# motor_control.net
KiCad netlist of a schematic drawn in Altium Designer
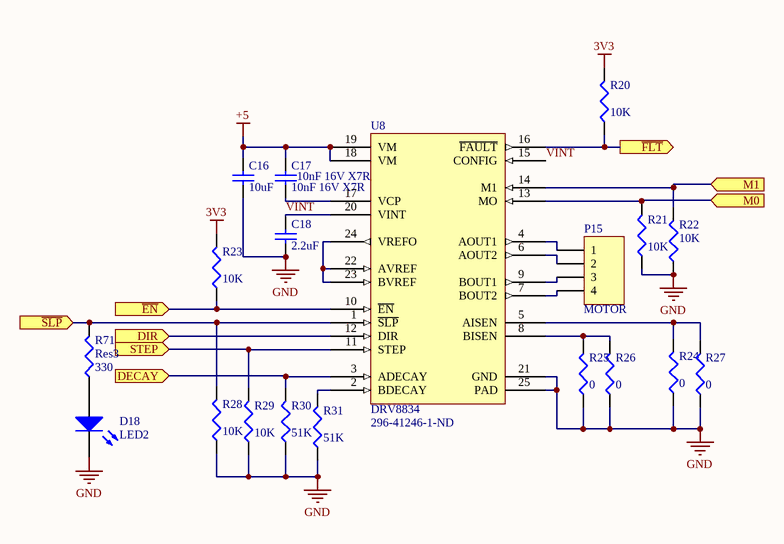
[diagram p0: motor_control.SchDoc]

(export (version "E")
  (design (tool "Eeschema 10.0.6"))
  (components
    (comp (ref "C16")
      (value "10uF")
      (footprint "1608[0603]")
      (description "Capacitor (Semiconductor SIM Model)")
      (fields (field (name "PUBLISHER") "Altium Limited"))
      (libsource (lib "Miscellaneous Devices") (part "Cap Semi"))
    )
    (comp (ref "C17")
      (value "10nF 16V X7R")
      (footprint "1608[0603]")
      (description "Capacitor (Semiconductor SIM Model)")
      (fields (field (name "ALTIUM_VALUE") "10nF 16V X7R") (field (name "PUBLISHER") "Altium Limited"))
      (libsource (lib "Miscellaneous Devices") (part "Cap Semi"))
    )
    (comp (ref "C18")
      (value "2.2uF")
      (footprint "1608[0603]")
      (description "Capacitor (Semiconductor SIM Model)")
      (fields (field (name "PUBLISHER") "Altium Limited"))
      (libsource (lib "Miscellaneous Devices") (part "Cap Semi"))
    )
    (comp (ref "D18")
      (value "LED2")
      (footprint "0603-LED")
      (description "Typical RED, GREEN, YELLOW, AMBER GaAs LED")
      (fields (field (name "PUBLISHER") "Altium Limited"))
      (libsource (lib "Miscellaneous Devices") (part "LED2"))
    )
    (comp (ref "P15")
      (value "MOTOR")
      (footprint "DF14-4P-1.25H(55)")
      (description "Header, 4-Pin")
      (fields (field (name "PUBLISHER") "Altium Limited"))
      (libsource (lib "Miscellaneous Connectors") (part "Header 4"))
    )
    (comp (ref "R20")
      (value "10K")
      (footprint "J1-0603")
      (description "Resistor")
      (fields (field (name "PUBLISHER") "Altium Limited"))
      (libsource (lib "Miscellaneous Devices") (part "Res3"))
    )
    (comp (ref "R21")
      (value "10K")
      (footprint "J1-0603")
      (description "Resistor")
      (fields (field (name "PUBLISHER") "Altium Limited"))
      (libsource (lib "Miscellaneous Devices") (part "Res3"))
    )
    (comp (ref "R22")
      (value "10K")
      (footprint "J1-0603")
      (description "Resistor")
      (fields (field (name "PUBLISHER") "Altium Limited"))
      (libsource (lib "Miscellaneous Devices") (part "Res3"))
    )
    (comp (ref "R23")
      (value "10K")
      (footprint "J1-0603")
      (description "Resistor")
      (fields (field (name "PUBLISHER") "Altium Limited"))
      (libsource (lib "Miscellaneous Devices") (part "Res3"))
    )
    (comp (ref "R24")
      (value "0")
      (footprint "J1-0603")
      (description "Resistor")
      (fields (field (name "PUBLISHER") "Altium Limited"))
      (libsource (lib "Miscellaneous Devices") (part "Res3"))
    )
    (comp (ref "R25")
      (value "0")
      (footprint "J1-0603")
      (description "Resistor")
      (fields (field (name "PUBLISHER") "Altium Limited"))
      (libsource (lib "Miscellaneous Devices") (part "Res3"))
    )
    (comp (ref "R26")
      (value "0")
      (footprint "J1-0603")
      (description "Resistor")
      (fields (field (name "PUBLISHER") "Altium Limited"))
      (libsource (lib "Miscellaneous Devices") (part "Res3"))
    )
    (comp (ref "R27")
      (value "0")
      (footprint "J1-0603")
      (description "Resistor")
      (fields (field (name "PUBLISHER") "Altium Limited"))
      (libsource (lib "Miscellaneous Devices") (part "Res3"))
    )
    (comp (ref "R28")
      (value "10K")
      (footprint "J1-0603")
      (description "Resistor")
      (fields (field (name "PUBLISHER") "Altium Limited"))
      (libsource (lib "Miscellaneous Devices") (part "Res3"))
    )
    (comp (ref "R29")
      (value "10K")
      (footprint "J1-0603")
      (description "Resistor")
      (fields (field (name "PUBLISHER") "Altium Limited"))
      (libsource (lib "Miscellaneous Devices") (part "Res3"))
    )
    (comp (ref "R30")
      (value "51K")
      (footprint "J1-0603")
      (description "Resistor")
      (fields (field (name "PUBLISHER") "Altium Limited"))
      (libsource (lib "Miscellaneous Devices") (part "Res3"))
    )
    (comp (ref "R31")
      (value "51K")
      (footprint "J1-0603")
      (description "Resistor")
      (fields (field (name "PUBLISHER") "Altium Limited"))
      (libsource (lib "Miscellaneous Devices") (part "Res3"))
    )
    (comp (ref "R71")
      (value "Res3")
      (footprint "J1-0603")
      (description "Resistor")
      (fields (field (name "ALTIUM_VALUE") "330") (field (name "PUBLISHER") "Altium Limited"))
      (libsource (lib "Miscellaneous Devices") (part "Res3"))
    )
    (comp (ref "U8")
      (value "DRV8834")
      (footprint "SOP65P640X120-25N")
      (description "Dual-bridge stepper or dc motor driver. 1.5A per coil with 2.5-10.8 V load supply.")
      (fields (field (name "SUPPLIER PART NUMBER 1") "296-41246-1-ND"))
      (libsource (lib "PAY") (part "DRV8834"))
    )
  )
  (nets
    (net (code "1") (name "+5") (class "Default")
      (node (ref "C16") (pin "2") (pinfunction "2_2") (pintype "passive"))
      (node (ref "C17") (pin "2") (pinfunction "2_2") (pintype "passive"))
      (node (ref "U8") (pin "18") (pinfunction "VM_18") (pintype "power_in"))
      (node (ref "U8") (pin "19") (pinfunction "VM_19") (pintype "power_in"))
    )
    (net (code "2") (name "/DECAY") (class "Default")
      (node (ref "R30") (pin "2") (pinfunction "2_2") (pintype "passive"))
      (node (ref "U8") (pin "3") (pinfunction "ADECAY_3") (pintype "input"))
    )
    (net (code "3") (name "/DIR") (class "Default")
      (node (ref "U8") (pin "12") (pinfunction "DIR_12") (pintype "input"))
    )
    (net (code "4") (name "/M0") (class "Default")
      (node (ref "R21") (pin "2") (pinfunction "2_2") (pintype "passive"))
      (node (ref "U8") (pin "13") (pinfunction "MO_13") (pintype "input"))
    )
    (net (code "5") (name "/M1") (class "Default")
      (node (ref "R22") (pin "2") (pinfunction "2_2") (pintype "passive"))
      (node (ref "U8") (pin "14") (pinfunction "M1_14") (pintype "input"))
    )
    (net (code "6") (name "/STEP") (class "Default")
      (node (ref "R29") (pin "2") (pinfunction "2_2") (pintype "passive"))
      (node (ref "U8") (pin "11") (pinfunction "STEP_11") (pintype "input"))
    )
    (net (code "7") (name "/VINT") (class "Default")
      (node (ref "C18") (pin "2") (pinfunction "2_2") (pintype "passive"))
      (node (ref "U8") (pin "15") (pinfunction "CONFIG_15") (pintype "input"))
      (node (ref "U8") (pin "20") (pinfunction "VINT_20") (pintype "power_in"))
    )
    (net (code "8") (name "/~{EN}") (class "Default")
      (node (ref "R23") (pin "1") (pinfunction "1_1") (pintype "passive"))
      (node (ref "U8") (pin "10") (pinfunction "~{EN}_10") (pintype "input"))
    )
    (net (code "9") (name "/~{FLT}") (class "Default")
      (node (ref "R20") (pin "1") (pinfunction "1_1") (pintype "passive"))
      (node (ref "U8") (pin "16") (pinfunction "~{FAULT}_16") (pintype "output"))
    )
    (net (code "10") (name "/~{SLP}") (class "Default")
      (node (ref "R28") (pin "2") (pinfunction "2_2") (pintype "passive"))
      (node (ref "R71") (pin "2") (pinfunction "2_2") (pintype "passive"))
      (node (ref "U8") (pin "1") (pinfunction "~{SLP}_1") (pintype "input"))
    )
    (net (code "11") (name "3V3") (class "Default")
      (node (ref "R20") (pin "2") (pinfunction "2_2") (pintype "passive"))
      (node (ref "R23") (pin "2") (pinfunction "2_2") (pintype "passive"))
    )
    (net (code "12") (name "GND") (class "Default")
      (node (ref "C16") (pin "1") (pinfunction "1_1") (pintype "passive"))
      (node (ref "C18") (pin "1") (pinfunction "1_1") (pintype "passive"))
      (node (ref "D18") (pin "2") (pinfunction "K_2") (pintype "passive"))
      (node (ref "R21") (pin "1") (pinfunction "1_1") (pintype "passive"))
      (node (ref "R22") (pin "1") (pinfunction "1_1") (pintype "passive"))
      (node (ref "R24") (pin "1") (pinfunction "1_1") (pintype "passive"))
      (node (ref "R25") (pin "1") (pinfunction "1_1") (pintype "passive"))
      (node (ref "R26") (pin "1") (pinfunction "1_1") (pintype "passive"))
      (node (ref "R27") (pin "1") (pinfunction "1_1") (pintype "passive"))
      (node (ref "R28") (pin "1") (pinfunction "1_1") (pintype "passive"))
      (node (ref "R29") (pin "1") (pinfunction "1_1") (pintype "passive"))
      (node (ref "R30") (pin "1") (pinfunction "1_1") (pintype "passive"))
      (node (ref "R31") (pin "1") (pinfunction "1_1") (pintype "passive"))
      (node (ref "U8") (pin "21") (pinfunction "GND_21") (pintype "power_in"))
      (node (ref "U8") (pin "25") (pinfunction "PAD_25") (pintype "power_in"))
    )
    (net (code "13") (name "Net-(D18-A)") (class "Default")
      (node (ref "D18") (pin "1") (pinfunction "A_1") (pintype "passive"))
      (node (ref "R71") (pin "1") (pinfunction "1_1") (pintype "passive"))
    )
    (net (code "14") (name "Net-(U8-AISEN)") (class "Default")
      (node (ref "R24") (pin "2") (pinfunction "2_2") (pintype "passive"))
      (node (ref "R27") (pin "2") (pinfunction "2_2") (pintype "passive"))
      (node (ref "U8") (pin "5") (pinfunction "AISEN_5") (pintype "passive"))
    )
    (net (code "15") (name "Net-(U8-AOUT1)") (class "Default")
      (node (ref "P15") (pin "1") (pinfunction "1_1") (pintype "passive"))
      (node (ref "U8") (pin "4") (pinfunction "AOUT1_4") (pintype "output"))
    )
    (net (code "16") (name "Net-(U8-AOUT2)") (class "Default")
      (node (ref "P15") (pin "2") (pinfunction "2_2") (pintype "passive"))
      (node (ref "U8") (pin "6") (pinfunction "AOUT2_6") (pintype "output"))
    )
    (net (code "17") (name "Net-(U8-AVREF)") (class "Default")
      (node (ref "U8") (pin "22") (pinfunction "AVREF_22") (pintype "input"))
      (node (ref "U8") (pin "23") (pinfunction "BVREF_23") (pintype "input"))
      (node (ref "U8") (pin "24") (pinfunction "VREFO_24") (pintype "output"))
    )
    (net (code "18") (name "Net-(U8-BDECAY)") (class "Default")
      (node (ref "R31") (pin "2") (pinfunction "2_2") (pintype "passive"))
      (node (ref "U8") (pin "2") (pinfunction "BDECAY_2") (pintype "input"))
    )
    (net (code "19") (name "Net-(U8-BISEN)") (class "Default")
      (node (ref "R25") (pin "2") (pinfunction "2_2") (pintype "passive"))
      (node (ref "R26") (pin "2") (pinfunction "2_2") (pintype "passive"))
      (node (ref "U8") (pin "8") (pinfunction "BISEN_8") (pintype "passive"))
    )
    (net (code "20") (name "Net-(U8-BOUT1)") (class "Default")
      (node (ref "P15") (pin "3") (pinfunction "3_3") (pintype "passive"))
      (node (ref "U8") (pin "9") (pinfunction "BOUT1_9") (pintype "output"))
    )
    (net (code "21") (name "Net-(U8-BOUT2)") (class "Default")
      (node (ref "P15") (pin "4") (pinfunction "4_4") (pintype "passive"))
      (node (ref "U8") (pin "7") (pinfunction "BOUT2_7") (pintype "output"))
    )
    (net (code "22") (name "Net-(U8-VCP)") (class "Default")
      (node (ref "C17") (pin "1") (pinfunction "1_1") (pintype "passive"))
      (node (ref "U8") (pin "17") (pinfunction "VCP_17") (pintype "power_in"))
    )
  )
)
